# ADC.net
KiCad netlist of a schematic drawn in Altium Designer
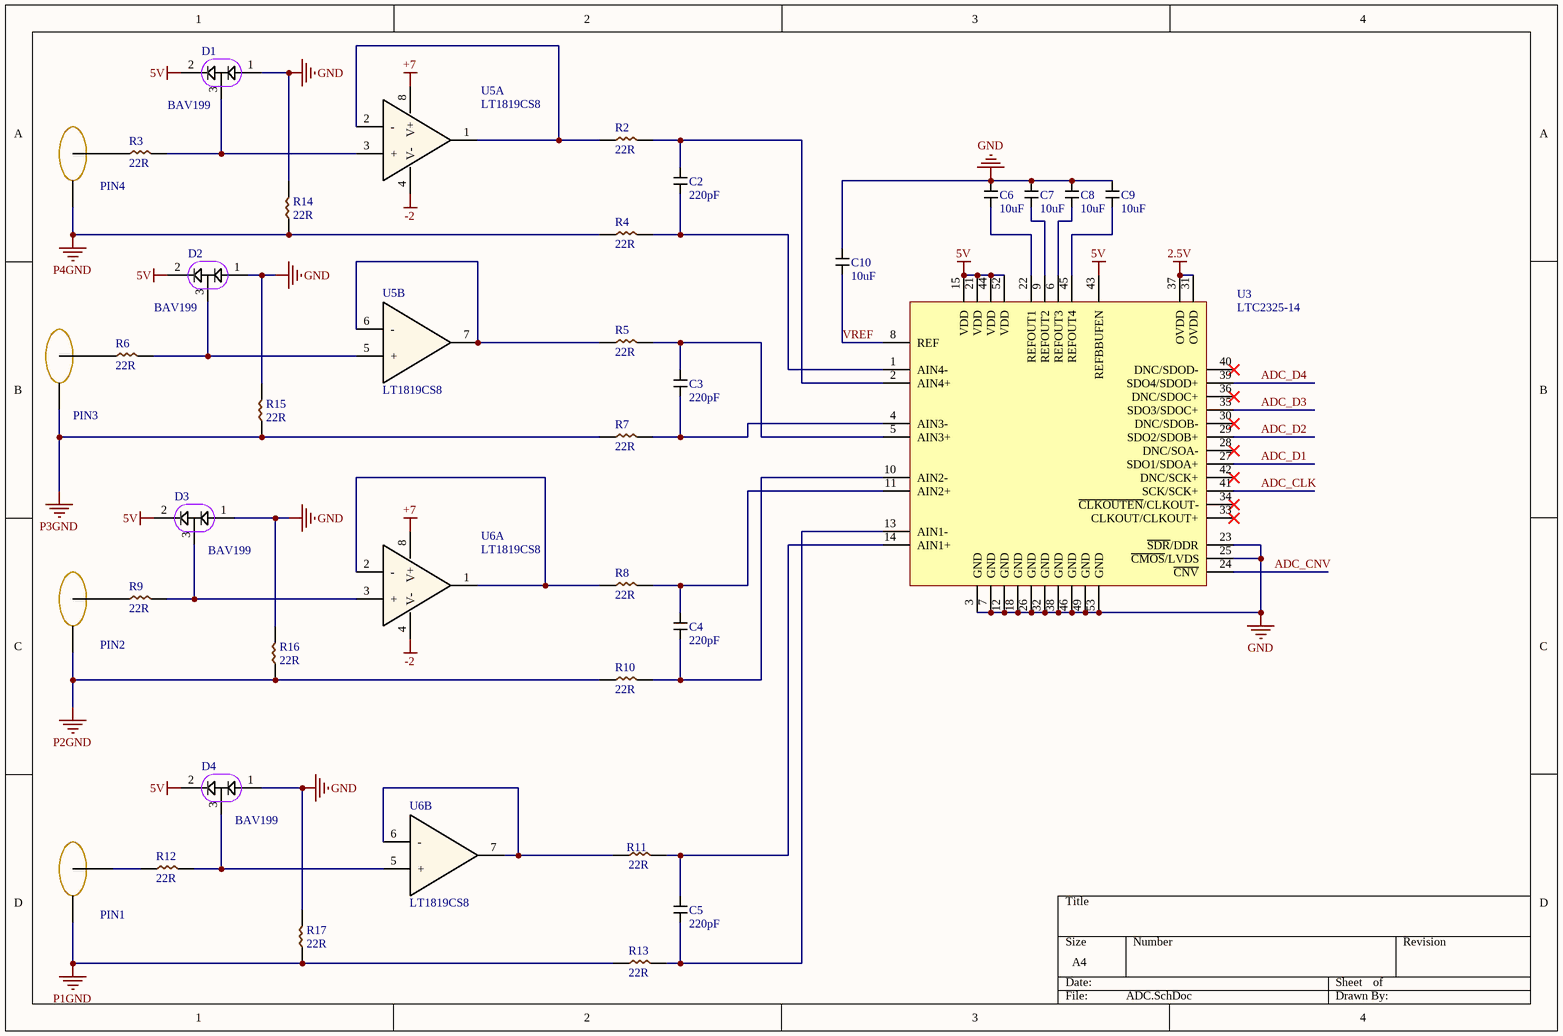
[diagram p0: ADC.SchDoc]

(export (version "E")
  (design (tool "Eeschema 10.0.6"))
  (components
    (comp (ref "C2") (value "220pF") (footprint "C0805") (libsource (lib "SMU") (part "C0805")))
    (comp (ref "C3") (value "220pF") (footprint "C0805") (libsource (lib "SMU") (part "C0805")))
    (comp (ref "C4") (value "220pF") (footprint "C0805") (libsource (lib "SMU") (part "C0805")))
    (comp (ref "C5") (value "220pF") (footprint "C0805") (libsource (lib "SMU") (part "C0805")))
    (comp (ref "C6") (value "10uF") (footprint "C0805") (libsource (lib "SMU") (part "C0805")))
    (comp (ref "C7") (value "10uF") (footprint "C0805") (libsource (lib "SMU") (part "C0805")))
    (comp (ref "C8") (value "10uF") (footprint "C0805") (libsource (lib "SMU") (part "C0805")))
    (comp (ref "C9") (value "10uF") (footprint "C0805") (libsource (lib "SMU") (part "C0805")))
    (comp (ref "C10") (value "10uF") (footprint "C0805") (libsource (lib "SMU") (part "C0805")))
    (comp (ref "D1") (value "BAV199") (footprint "SOT23-3") (libsource (lib "SMU") (part "BAV199")))
    (comp (ref "D2") (value "BAV199") (footprint "SOT23-3") (libsource (lib "SMU") (part "BAV199")))
    (comp (ref "D3") (value "BAV199") (footprint "SOT23-3") (libsource (lib "SMU") (part "BAV199")))
    (comp (ref "D4") (value "BAV199") (footprint "SOT23-3") (libsource (lib "SMU") (part "BAV199")))
    (comp (ref "PIN1")
      (value "PCB.SMAFRA.HT")
      (footprint "PCB.SMAFRA.HT")
      (libsource (lib "OpenSEM") (part "PCB.SMAFRA.HT"))
    )
    (comp (ref "PIN2")
      (value "PCB.SMAFRA.HT")
      (footprint "PCB.SMAFRA.HT")
      (libsource (lib "OpenSEM") (part "PCB.SMAFRA.HT"))
    )
    (comp (ref "PIN3")
      (value "PCB.SMAFRA.HT")
      (footprint "PCB.SMAFRA.HT")
      (libsource (lib "OpenSEM") (part "PCB.SMAFRA.HT"))
    )
    (comp (ref "PIN4")
      (value "PCB.SMAFRA.HT")
      (footprint "PCB.SMAFRA.HT")
      (libsource (lib "OpenSEM") (part "PCB.SMAFRA.HT"))
    )
    (comp (ref "R2") (value "22R") (footprint "R0805") (libsource (lib "SMU") (part "R0805")))
    (comp (ref "R3") (value "22R") (footprint "R0805") (libsource (lib "SMU") (part "R0805")))
    (comp (ref "R4") (value "22R") (footprint "R0805") (libsource (lib "SMU") (part "R0805")))
    (comp (ref "R5") (value "22R") (footprint "R0805") (libsource (lib "SMU") (part "R0805")))
    (comp (ref "R6") (value "22R") (footprint "R0805") (libsource (lib "SMU") (part "R0805")))
    (comp (ref "R7") (value "22R") (footprint "R0805") (libsource (lib "SMU") (part "R0805")))
    (comp (ref "R8") (value "22R") (footprint "R0805") (libsource (lib "SMU") (part "R0805")))
    (comp (ref "R9") (value "22R") (footprint "R0805") (libsource (lib "SMU") (part "R0805")))
    (comp (ref "R10") (value "22R") (footprint "R0805") (libsource (lib "SMU") (part "R0805")))
    (comp (ref "R11") (value "22R") (footprint "R0805") (libsource (lib "SMU") (part "R0805")))
    (comp (ref "R12") (value "22R") (footprint "R0805") (libsource (lib "SMU") (part "R0805")))
    (comp (ref "R13") (value "22R") (footprint "R0805") (libsource (lib "SMU") (part "R0805")))
    (comp (ref "R14") (value "22R") (footprint "R0805") (libsource (lib "SMU") (part "R0805")))
    (comp (ref "R15") (value "22R") (footprint "R0805") (libsource (lib "SMU") (part "R0805")))
    (comp (ref "R16") (value "22R") (footprint "R0805") (libsource (lib "SMU") (part "R0805")))
    (comp (ref "R17") (value "22R") (footprint "R0805") (libsource (lib "SMU") (part "R0805")))
    (comp (ref "U3")
      (value "LTC2325-14")
      (footprint "QFN-52")
      (description "Quad, 14-Bit + Sign, 5Msps/Ch\r\nSimultaneous Sampling ADC")
      (libsource (lib "OpenSEM") (part "LTC2325-14"))
    )
    (comp (ref "U5") (value "LT1819CS8") (footprint "SOIC-8") (libsource (lib "OpenSEM") (part "LT1819CS8")))
    (comp (ref "U6") (value "LT1819CS8") (footprint "SOIC-8") (libsource (lib "OpenSEM") (part "LT1819CS8")))
  )
  (nets
    (net (code "1") (name "+7") (class "Default")
      (node (ref "U5") (pin "8") (pinfunction "V+_8") (pintype "passive"))
      (node (ref "U6") (pin "8") (pinfunction "V+_8") (pintype "passive"))
    )
    (net (code "2") (name "-2") (class "Default")
      (node (ref "U5") (pin "4") (pinfunction "V-_4") (pintype "passive"))
      (node (ref "U6") (pin "4") (pinfunction "V-_4") (pintype "passive"))
    )
    (net (code "3") (name "/ADC_CLK") (class "Default")
      (node (ref "U3") (pin "41") (pinfunction "SCK/SCK+_41") (pintype "passive"))
    )
    (net (code "4") (name "/ADC_CNV") (class "Default")
      (node (ref "U3") (pin "24") (pinfunction "~{CNV}_24") (pintype "passive"))
    )
    (net (code "5") (name "/ADC_D1") (class "Default")
      (node (ref "U3") (pin "27") (pinfunction "SDO1/SDOA+_27") (pintype "passive"))
    )
    (net (code "6") (name "/ADC_D2") (class "Default")
      (node (ref "U3") (pin "29") (pinfunction "SDO2/SDOB+_29") (pintype "passive"))
    )
    (net (code "7") (name "/ADC_D3") (class "Default")
      (node (ref "U3") (pin "35") (pinfunction "SDO3/SDOC+_35") (pintype "passive"))
    )
    (net (code "8") (name "/ADC_D4") (class "Default")
      (node (ref "U3") (pin "39") (pinfunction "SDO4/SDOD+_39") (pintype "passive"))
    )
    (net (code "9") (name "/VREF") (class "Default")
      (node (ref "C10") (pin "1") (pintype "passive"))
      (node (ref "U3") (pin "8") (pinfunction "REF_8") (pintype "passive"))
    )
    (net (code "10") (name "2.5V") (class "Default")
      (node (ref "U3") (pin "31") (pinfunction "OVDD_31") (pintype "passive"))
      (node (ref "U3") (pin "37") (pinfunction "OVDD_37") (pintype "passive"))
    )
    (net (code "11") (name "5V") (class "Default")
      (node (ref "D1") (pin "2") (pintype "passive"))
      (node (ref "D2") (pin "2") (pintype "passive"))
      (node (ref "D3") (pin "2") (pintype "passive"))
      (node (ref "D4") (pin "2") (pintype "passive"))
      (node (ref "U3") (pin "15") (pinfunction "VDD_15") (pintype "passive"))
      (node (ref "U3") (pin "21") (pinfunction "VDD_21") (pintype "passive"))
      (node (ref "U3") (pin "43") (pinfunction "REFBBUFEN_43") (pintype "passive"))
      (node (ref "U3") (pin "44") (pinfunction "VDD_44") (pintype "passive"))
      (node (ref "U3") (pin "52") (pinfunction "VDD_52") (pintype "passive"))
    )
    (net (code "12") (name "GND") (class "Default")
      (node (ref "C10") (pin "2") (pintype "passive"))
      (node (ref "C6") (pin "2") (pintype "passive"))
      (node (ref "C7") (pin "2") (pintype "passive"))
      (node (ref "C8") (pin "2") (pintype "passive"))
      (node (ref "C9") (pin "2") (pintype "passive"))
      (node (ref "D1") (pin "1") (pintype "passive"))
      (node (ref "D2") (pin "1") (pintype "passive"))
      (node (ref "D3") (pin "1") (pintype "passive"))
      (node (ref "D4") (pin "1") (pintype "passive"))
      (node (ref "R14") (pin "2") (pintype "passive"))
      (node (ref "R15") (pin "2") (pintype "passive"))
      (node (ref "R16") (pin "2") (pintype "passive"))
      (node (ref "R17") (pin "2") (pintype "passive"))
      (node (ref "U3") (pin "12") (pinfunction "GND_12") (pintype "passive"))
      (node (ref "U3") (pin "18") (pinfunction "GND_18") (pintype "passive"))
      (node (ref "U3") (pin "23") (pinfunction "~{SDR}/DDR_23") (pintype "passive"))
      (node (ref "U3") (pin "25") (pinfunction "~{CMOS}/LVDS_25") (pintype "passive"))
      (node (ref "U3") (pin "26") (pinfunction "GND_26") (pintype "passive"))
      (node (ref "U3") (pin "3") (pinfunction "GND_3") (pintype "passive"))
      (node (ref "U3") (pin "32") (pinfunction "GND_32") (pintype "passive"))
      (node (ref "U3") (pin "38") (pinfunction "GND_38") (pintype "passive"))
      (node (ref "U3") (pin "46") (pinfunction "GND_46") (pintype "passive"))
      (node (ref "U3") (pin "49") (pinfunction "GND_49") (pintype "passive"))
      (node (ref "U3") (pin "53") (pinfunction "GND_53") (pintype "passive"))
      (node (ref "U3") (pin "7") (pinfunction "GND_7") (pintype "passive"))
    )
    (net (code "13") (name "Net-(PIN1-Pad1)") (class "Default")
      (node (ref "PIN1") (pin "1") (pinfunction "1_1") (pintype "passive"))
      (node (ref "R12") (pin "1") (pintype "passive"))
    )
    (net (code "14") (name "Net-(PIN2-Pad1)") (class "Default")
      (node (ref "PIN2") (pin "1") (pinfunction "1_1") (pintype "passive"))
      (node (ref "R9") (pin "1") (pintype "passive"))
    )
    (net (code "15") (name "Net-(PIN3-Pad1)") (class "Default")
      (node (ref "PIN3") (pin "1") (pinfunction "1_1") (pintype "passive"))
      (node (ref "R6") (pin "1") (pintype "passive"))
    )
    (net (code "16") (name "Net-(PIN4-Pad1)") (class "Default")
      (node (ref "PIN4") (pin "1") (pinfunction "1_1") (pintype "passive"))
      (node (ref "R3") (pin "1") (pintype "passive"))
    )
    (net (code "17") (name "Net-(U3-AIN1+)") (class "Default")
      (node (ref "C5") (pin "2") (pintype "passive"))
      (node (ref "R11") (pin "2") (pintype "passive"))
      (node (ref "U3") (pin "14") (pinfunction "AIN1+_14") (pintype "passive"))
    )
    (net (code "18") (name "Net-(U3-AIN1-)") (class "Default")
      (node (ref "C5") (pin "1") (pintype "passive"))
      (node (ref "R13") (pin "2") (pintype "passive"))
      (node (ref "U3") (pin "13") (pinfunction "AIN1-_13") (pintype "passive"))
    )
    (net (code "19") (name "Net-(U3-AIN2+)") (class "Default")
      (node (ref "C4") (pin "2") (pintype "passive"))
      (node (ref "R8") (pin "2") (pintype "passive"))
      (node (ref "U3") (pin "11") (pinfunction "AIN2+_11") (pintype "passive"))
    )
    (net (code "20") (name "Net-(U3-AIN2-)") (class "Default")
      (node (ref "C4") (pin "1") (pintype "passive"))
      (node (ref "R10") (pin "2") (pintype "passive"))
      (node (ref "U3") (pin "10") (pinfunction "AIN2-_10") (pintype "passive"))
    )
    (net (code "21") (name "Net-(U3-AIN3+)") (class "Default")
      (node (ref "C3") (pin "2") (pintype "passive"))
      (node (ref "R5") (pin "2") (pintype "passive"))
      (node (ref "U3") (pin "5") (pinfunction "AIN3+_5") (pintype "passive"))
    )
    (net (code "22") (name "Net-(U3-AIN3-)") (class "Default")
      (node (ref "C3") (pin "1") (pintype "passive"))
      (node (ref "R7") (pin "2") (pintype "passive"))
      (node (ref "U3") (pin "4") (pinfunction "AIN3-_4") (pintype "passive"))
    )
    (net (code "23") (name "Net-(U3-AIN4+)") (class "Default")
      (node (ref "C2") (pin "2") (pintype "passive"))
      (node (ref "R2") (pin "2") (pintype "passive"))
      (node (ref "U3") (pin "2") (pinfunction "AIN4+_2") (pintype "passive"))
    )
    (net (code "24") (name "Net-(U3-AIN4-)") (class "Default")
      (node (ref "C2") (pin "1") (pintype "passive"))
      (node (ref "R4") (pin "2") (pintype "passive"))
      (node (ref "U3") (pin "1") (pinfunction "AIN4-_1") (pintype "passive"))
    )
    (net (code "25") (name "Net-(U3-REFOUT1)") (class "Default")
      (node (ref "C6") (pin "1") (pintype "passive"))
      (node (ref "U3") (pin "22") (pinfunction "REFOUT1_22") (pintype "passive"))
    )
    (net (code "26") (name "Net-(U3-REFOUT2)") (class "Default")
      (node (ref "C7") (pin "1") (pintype "passive"))
      (node (ref "U3") (pin "9") (pinfunction "REFOUT2_9") (pintype "passive"))
    )
    (net (code "27") (name "Net-(U3-REFOUT3)") (class "Default")
      (node (ref "C8") (pin "1") (pintype "passive"))
      (node (ref "U3") (pin "6") (pinfunction "REFOUT3_6") (pintype "passive"))
    )
    (net (code "28") (name "Net-(U3-REFOUT4)") (class "Default")
      (node (ref "C9") (pin "1") (pintype "passive"))
      (node (ref "U3") (pin "45") (pinfunction "REFOUT4_45") (pintype "passive"))
    )
    (net (code "29") (name "Net-(U5A-+)") (class "Default")
      (node (ref "D1") (pin "3") (pintype "passive"))
      (node (ref "R3") (pin "2") (pintype "passive"))
      (node (ref "U5") (pin "3") (pinfunction "+_3") (pintype "passive"))
    )
    (net (code "30") (name "Net-(U5A--)") (class "Default")
      (node (ref "R2") (pin "1") (pintype "passive"))
      (node (ref "U5") (pin "1") (pintype "passive"))
      (node (ref "U5") (pin "2") (pinfunction "-_2") (pintype "passive"))
    )
    (net (code "31") (name "Net-(U5B-+)") (class "Default")
      (node (ref "D2") (pin "3") (pintype "passive"))
      (node (ref "R6") (pin "2") (pintype "passive"))
      (node (ref "U5") (pin "5") (pinfunction "+_5") (pintype "passive"))
    )
    (net (code "32") (name "Net-(U5B--)") (class "Default")
      (node (ref "R5") (pin "1") (pintype "passive"))
      (node (ref "U5") (pin "6") (pinfunction "-_6") (pintype "passive"))
      (node (ref "U5") (pin "7") (pintype "passive"))
    )
    (net (code "33") (name "Net-(U6A-+)") (class "Default")
      (node (ref "D3") (pin "3") (pintype "passive"))
      (node (ref "R9") (pin "2") (pintype "passive"))
      (node (ref "U6") (pin "3") (pinfunction "+_3") (pintype "passive"))
    )
    (net (code "34") (name "Net-(U6A--)") (class "Default")
      (node (ref "R8") (pin "1") (pintype "passive"))
      (node (ref "U6") (pin "1") (pintype "passive"))
      (node (ref "U6") (pin "2") (pinfunction "-_2") (pintype "passive"))
    )
    (net (code "35") (name "Net-(U6B-+)") (class "Default")
      (node (ref "D4") (pin "3") (pintype "passive"))
      (node (ref "R12") (pin "2") (pintype "passive"))
      (node (ref "U6") (pin "5") (pinfunction "+_5") (pintype "passive"))
    )
    (net (code "36") (name "Net-(U6B--)") (class "Default")
      (node (ref "R11") (pin "1") (pintype "passive"))
      (node (ref "U6") (pin "6") (pinfunction "-_6") (pintype "passive"))
      (node (ref "U6") (pin "7") (pintype "passive"))
    )
    (net (code "37") (name "P1GND") (class "Default")
      (node (ref "PIN1") (pin "S") (pinfunction "S_S") (pintype "passive"))
      (node (ref "R13") (pin "1") (pintype "passive"))
      (node (ref "R17") (pin "1") (pintype "passive"))
    )
    (net (code "38") (name "P2GND") (class "Default")
      (node (ref "PIN2") (pin "S") (pinfunction "S_S") (pintype "passive"))
      (node (ref "R10") (pin "1") (pintype "passive"))
      (node (ref "R16") (pin "1") (pintype "passive"))
    )
    (net (code "39") (name "P3GND") (class "Default")
      (node (ref "PIN3") (pin "S") (pinfunction "S_S") (pintype "passive"))
      (node (ref "R15") (pin "1") (pintype "passive"))
      (node (ref "R7") (pin "1") (pintype "passive"))
    )
    (net (code "40") (name "P4GND") (class "Default")
      (node (ref "PIN4") (pin "S") (pinfunction "S_S") (pintype "passive"))
      (node (ref "R14") (pin "1") (pintype "passive"))
      (node (ref "R4") (pin "1") (pintype "passive"))
    )
    (net (code "41") (name "unconnected-(U3-CLKOUT{slash}CLKOUT+-Pad33)") (class "Default")
      (node (ref "U3") (pin "33") (pinfunction "CLKOUT/CLKOUT+_33") (pintype "passive+no_connect"))
    )
    (net (code "42") (name "unconnected-(U3-DNC{slash}SCK+-Pad42)") (class "Default")
      (node (ref "U3") (pin "42") (pinfunction "DNC/SCK+_42") (pintype "passive+no_connect"))
    )
    (net (code "43") (name "unconnected-(U3-DNC{slash}SDOB--Pad30)") (class "Default")
      (node (ref "U3") (pin "30") (pinfunction "DNC/SDOB-_30") (pintype "passive+no_connect"))
    )
    (net (code "44") (name "unconnected-(U3-DNC{slash}SDOC+-Pad36)") (class "Default")
      (node (ref "U3") (pin "36") (pinfunction "DNC/SDOC+_36") (pintype "passive+no_connect"))
    )
    (net (code "45") (name "unconnected-(U3-DNC{slash}SDOD--Pad40)") (class "Default")
      (node (ref "U3") (pin "40") (pinfunction "DNC/SDOD-_40") (pintype "passive+no_connect"))
    )
    (net (code "46") (name "unconnected-(U3-DNC{slash}SOA--Pad28)") (class "Default")
      (node (ref "U3") (pin "28") (pinfunction "DNC/SOA-_28") (pintype "passive+no_connect"))
    )
    (net (code "47") (name "unconnected-(U3-~{CLKOUTEN}{slash}CLKOUT--Pad34)") (class "Default")
      (node (ref "U3") (pin "34") (pinfunction "~{CLKOUTEN}/CLKOUT-_34") (pintype "passive+no_connect"))
    )
  )
)
